# MCU_4G_SEN.net
KiCad netlist of a schematic drawn in Altium Designer
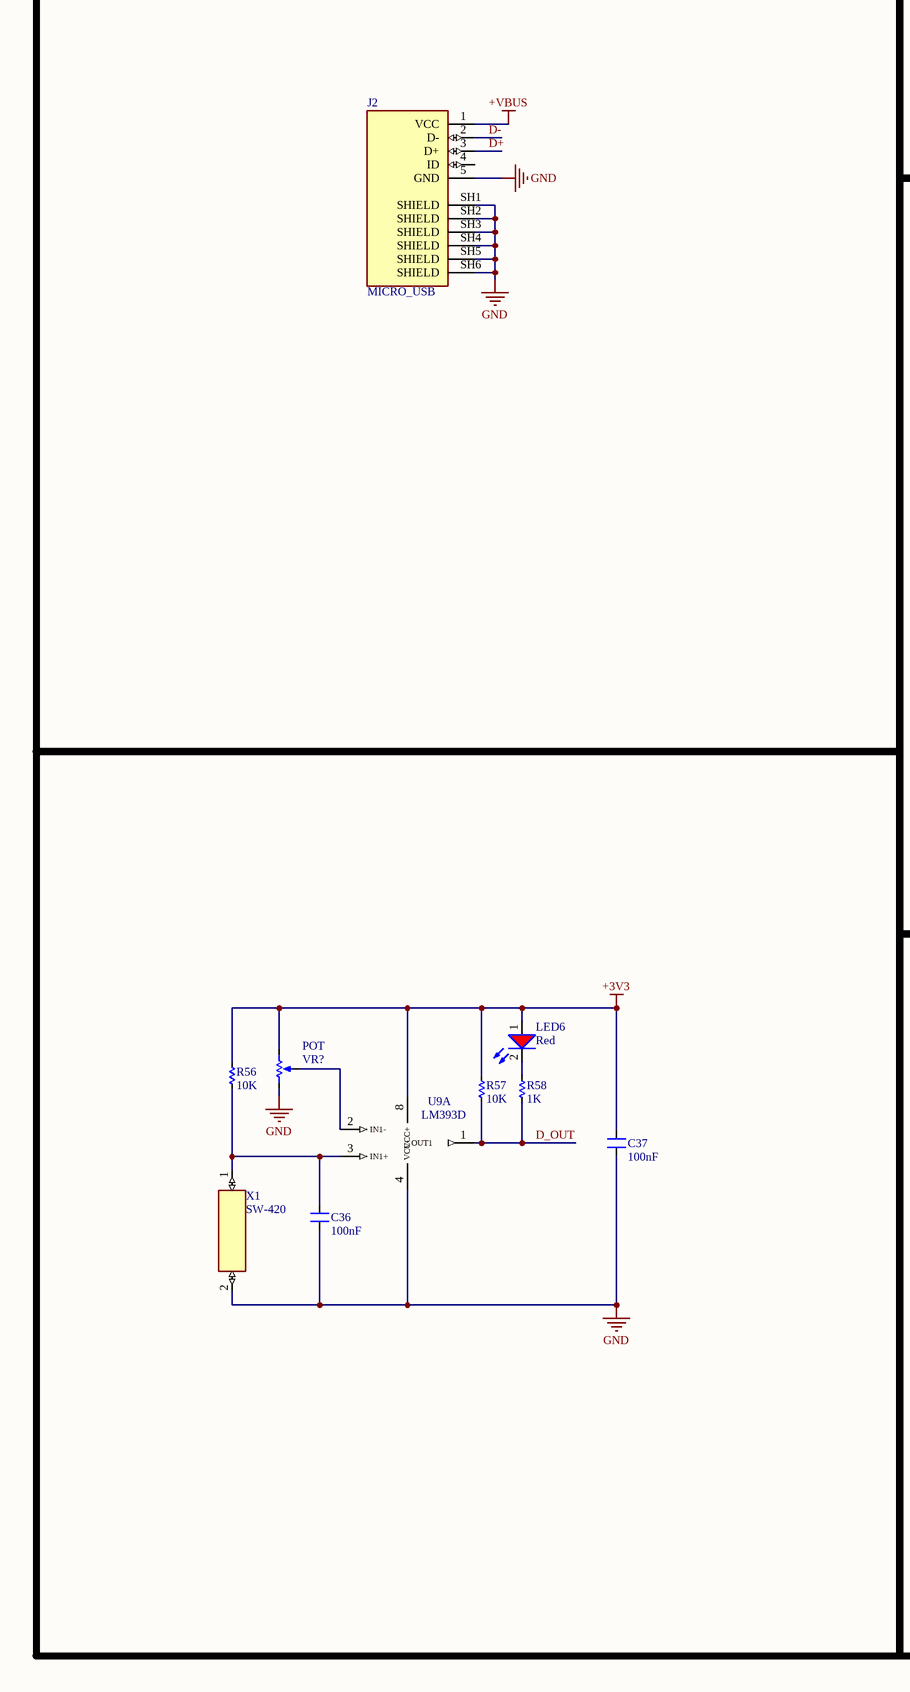
[diagram p0: MCU_4G_SEN.SchDoc, left]
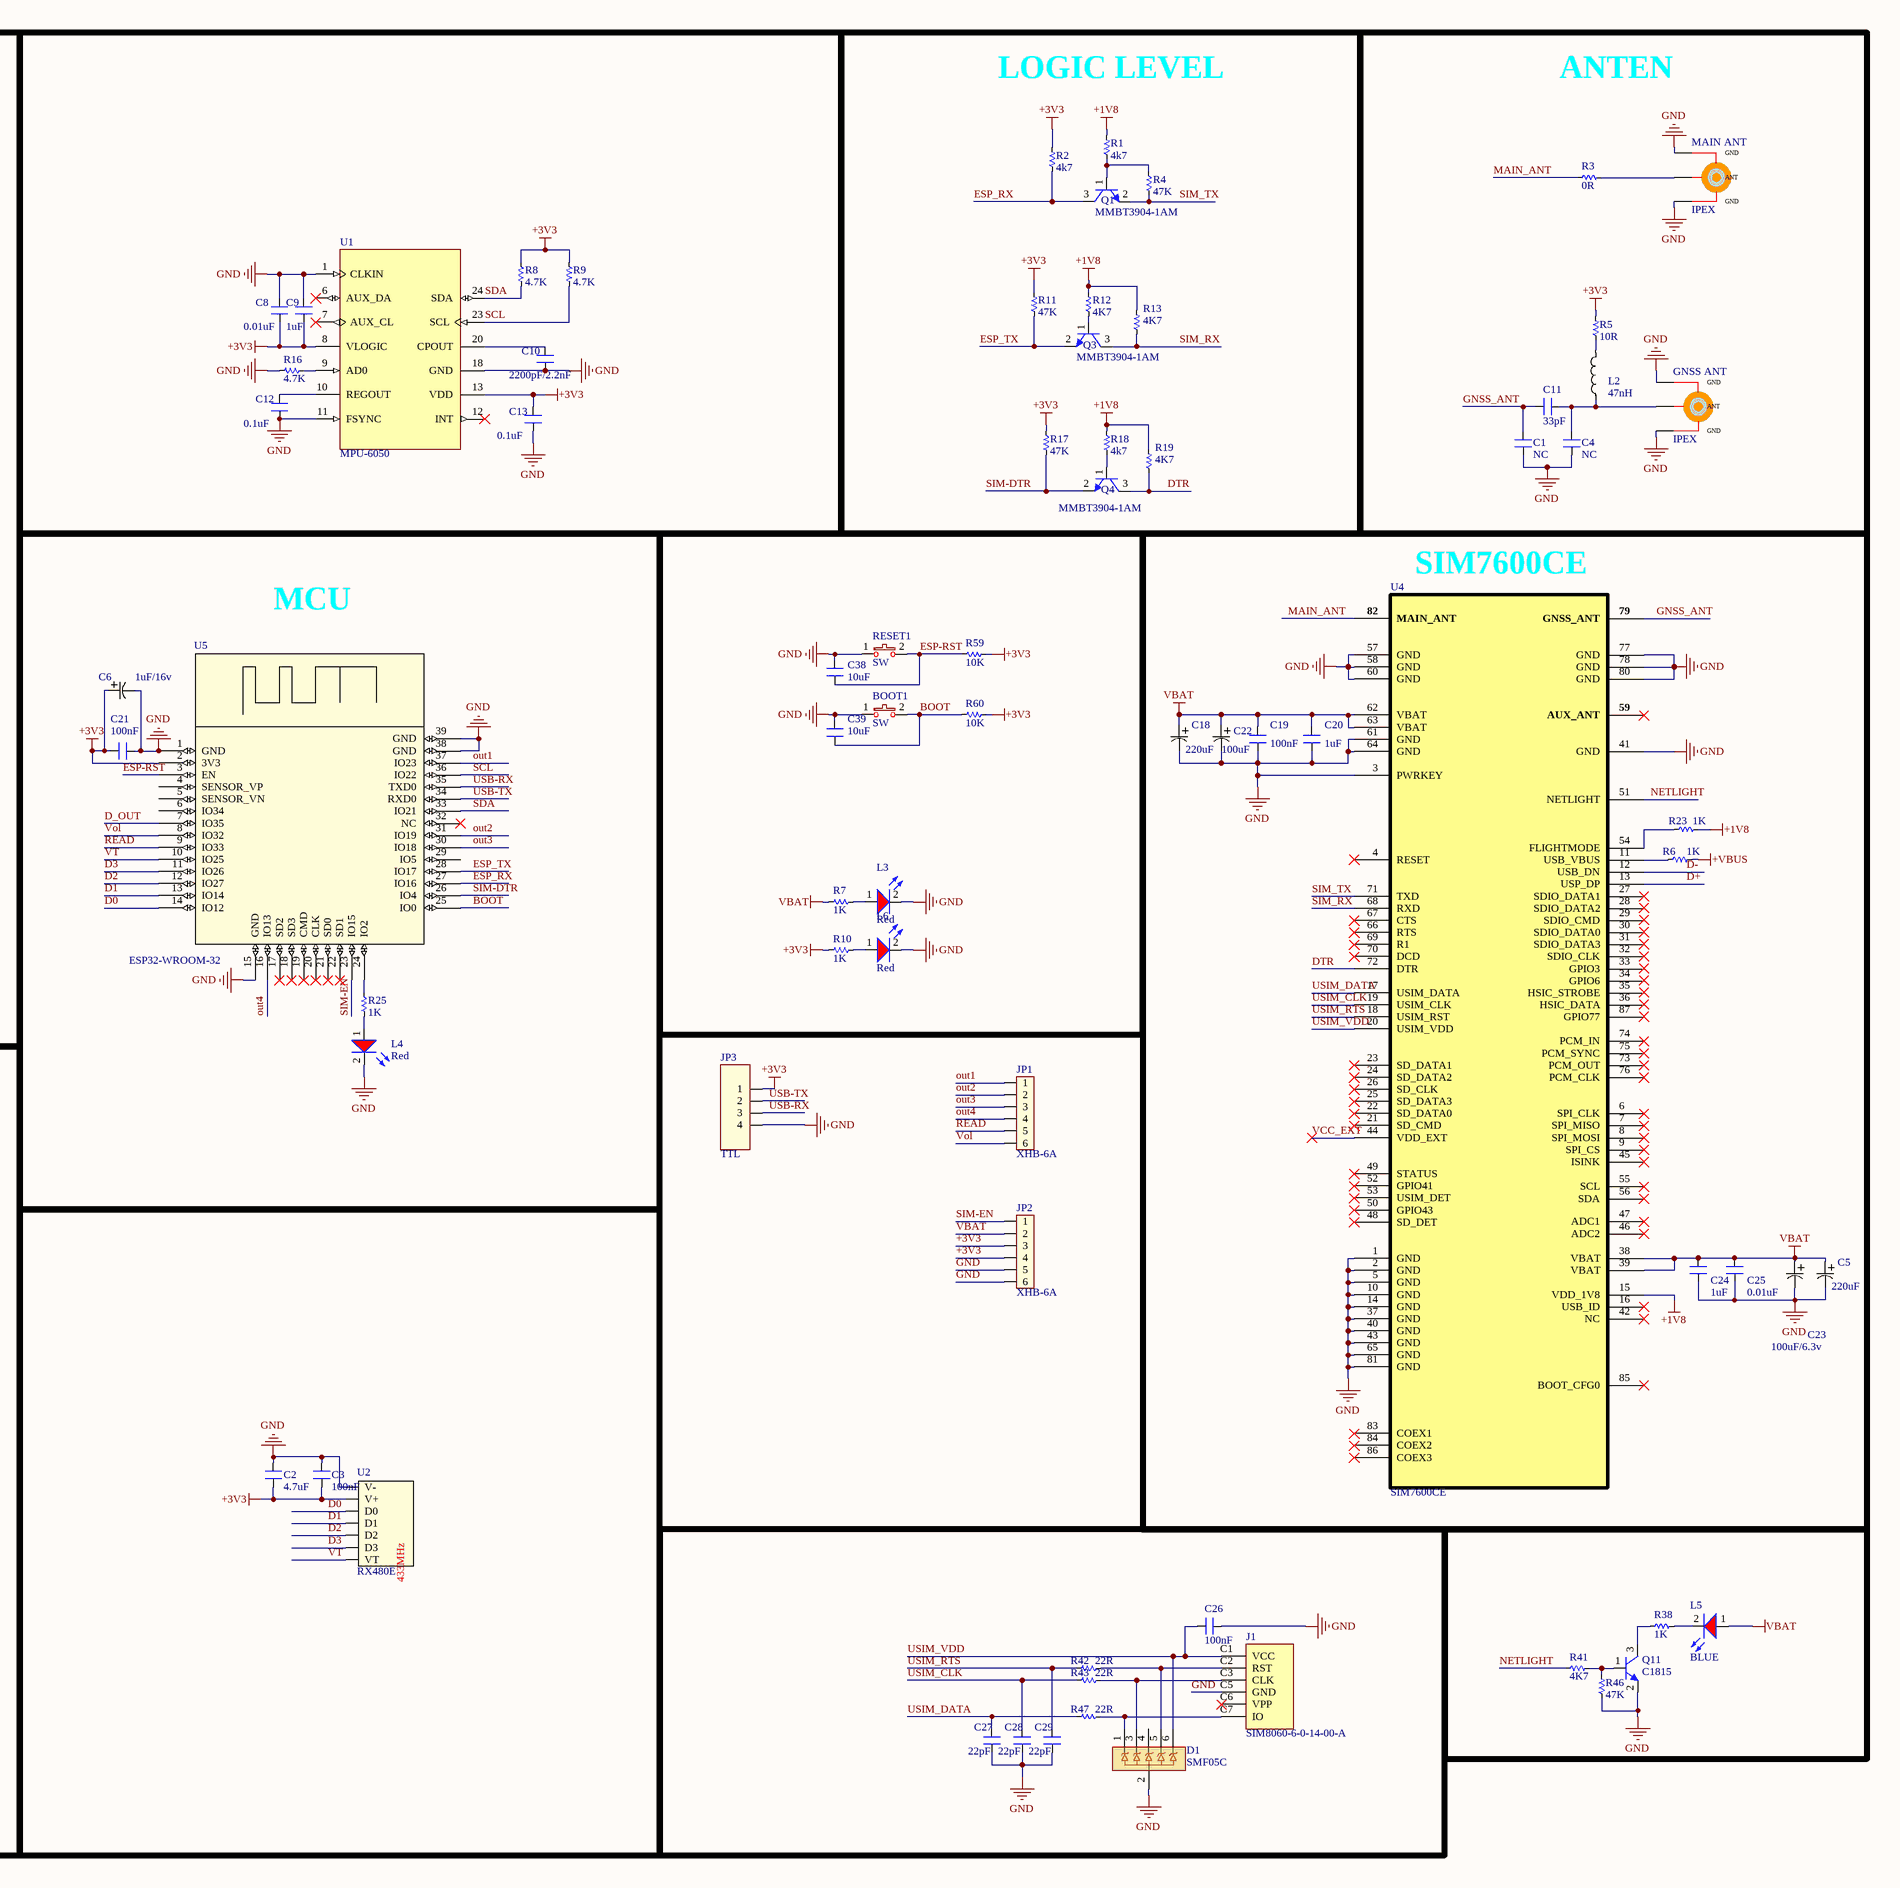
[diagram p1: MCU_4G_SEN.SchDoc, right]

(export (version "E")
  (design (tool "Eeschema 10.0.6"))
  (components
    (comp (ref "BOOT1")
      (value "SW")
      (footprint "BUTTON_3X4MM_2PIN")
      (libsource (lib "tuananh_smd") (part "BUTON2"))
    )
    (comp (ref "C1")
      (value "NC")
      (footprint "CAP-0603")
      (description "Cap np W0.3")
      (fields (field (name "COPYRIGHT") "VanDungEvn"))
      (libsource (lib "tuananh_smd") (part "CAP ko phan cuc"))
    )
    (comp (ref "C2")
      (value "4.7uF")
      (footprint "CAP-0603")
      (description "Cap np W0.3")
      (fields (field (name "COPYRIGHT") "VanDungEvn"))
      (libsource (lib "tuananh_smd") (part "CAP ko phan cuc"))
    )
    (comp (ref "C3")
      (value "100nF")
      (footprint "CAP-0603")
      (description "Cap np W0.3")
      (fields (field (name "COPYRIGHT") "VanDungEvn"))
      (libsource (lib "tuananh_smd") (part "CAP ko phan cuc"))
    )
    (comp (ref "C4")
      (value "NC")
      (footprint "CAP-0603")
      (description "Cap np W0.3")
      (fields (field (name "COPYRIGHT") "VanDungEvn"))
      (libsource (lib "tuananh_smd") (part "CAP ko phan cuc"))
    )
    (comp (ref "C5")
      (value "220uF")
      (footprint "CAP-TANTALUM-2312 - ( 6032M )")
      (libsource (lib "Tuấn Anh") (part "CAP_PHANCUCDEN"))
    )
    (comp (ref "C6")
      (value "1uF/16v")
      (footprint "CAP-TANTALUM-1206 - ( 3216 )")
      (libsource (lib "") (part "CAP_PHANCUCDEN_1"))
    )
    (comp (ref "C8")
      (value "0.01uF")
      (footprint "CAP-0603")
      (description "Cap np W0.3")
      (fields (field (name "COPYRIGHT") "VanDungEvn"))
      (libsource (lib "tuananh_smd") (part "CAP ko phan cuc"))
    )
    (comp (ref "C9")
      (value "1uF")
      (footprint "CAP-0603")
      (description "Cap np W0.3")
      (fields (field (name "COPYRIGHT") "VanDungEvn"))
      (libsource (lib "tuananh_smd") (part "CAP ko phan cuc"))
    )
    (comp (ref "C10")
      (value "2200pF/2.2nF")
      (footprint "CAP-0603")
      (description "Cap np W0.3")
      (fields (field (name "COPYRIGHT") "VanDungEvn"))
      (libsource (lib "tuananh_smd") (part "CAP ko phan cuc"))
    )
    (comp (ref "C11")
      (value "33pF")
      (footprint "CAP-0603")
      (description "Cap np W0.3")
      (fields (field (name "COPYRIGHT") "VanDungEvn"))
      (libsource (lib "tuananh_smd") (part "CAP ko phan cuc"))
    )
    (comp (ref "C12")
      (value "0.1uF")
      (footprint "CAP-0603")
      (description "Cap np W0.3")
      (fields (field (name "COPYRIGHT") "VanDungEvn"))
      (libsource (lib "tuananh_smd") (part "CAP ko phan cuc"))
    )
    (comp (ref "C13")
      (value "0.1uF")
      (footprint "CAP-0603")
      (description "Cap np W0.3")
      (fields (field (name "COPYRIGHT") "VanDungEvn"))
      (libsource (lib "tuananh_smd") (part "CAP ko phan cuc"))
    )
    (comp (ref "C18")
      (value "220uF")
      (footprint "CAP-TANTALUM-2312 - ( 6032M )")
      (libsource (lib "Tuấn Anh") (part "CAP_PHANCUCDEN"))
    )
    (comp (ref "C19")
      (value "100nF")
      (footprint "CAP-0603")
      (description "Cap np W0.3")
      (fields (field (name "COPYRIGHT") "VanDungEvn"))
      (libsource (lib "tuananh_smd") (part "CAP ko phan cuc"))
    )
    (comp (ref "C20")
      (value "1uF")
      (footprint "CAP-0603")
      (description "Cap np W0.3")
      (fields (field (name "COPYRIGHT") "VanDungEvn"))
      (libsource (lib "tuananh_smd") (part "CAP ko phan cuc"))
    )
    (comp (ref "C21")
      (value "100nF")
      (footprint "CAP-0603")
      (description "Cap np W0.3")
      (fields (field (name "COPYRIGHT") "VanDungEvn"))
      (libsource (lib "tuananh_smd") (part "CAP ko phan cuc"))
    )
    (comp (ref "C22")
      (value "100uF")
      (footprint "CAP-TANTALUM-1206 - ( 3216 )")
      (libsource (lib "Tuấn Anh") (part "CAP_PHANCUCDEN"))
    )
    (comp (ref "C23")
      (value "100uF/6.3v")
      (footprint "CAP-TANTALUM-1206 - ( 3216 )")
      (libsource (lib "Tuấn Anh") (part "CAP_PHANCUCDEN"))
    )
    (comp (ref "C24")
      (value "1uF")
      (footprint "CAP-0603")
      (description "Cap np W0.3")
      (fields (field (name "COPYRIGHT") "VanDungEvn"))
      (libsource (lib "tuananh_smd") (part "CAP ko phan cuc"))
    )
    (comp (ref "C25")
      (value "0.01uF")
      (footprint "CAP-0603")
      (description "Cap np W0.3")
      (fields (field (name "COPYRIGHT") "VanDungEvn"))
      (libsource (lib "tuananh_smd") (part "CAP ko phan cuc"))
    )
    (comp (ref "C26")
      (value "100nF")
      (footprint "CAP-0603")
      (description "Cap np W0.3")
      (fields (field (name "COPYRIGHT") "VanDungEvn"))
      (libsource (lib "tuananh_smd") (part "CAP ko phan cuc"))
    )
    (comp (ref "C27")
      (value "22pF")
      (footprint "CAP-0603")
      (description "Cap np W0.3")
      (fields (field (name "COPYRIGHT") "VanDungEvn"))
      (libsource (lib "tuananh_smd") (part "CAP ko phan cuc"))
    )
    (comp (ref "C28")
      (value "22pF")
      (footprint "CAP-0603")
      (description "Cap np W0.3")
      (fields (field (name "COPYRIGHT") "VanDungEvn"))
      (libsource (lib "tuananh_smd") (part "CAP ko phan cuc"))
    )
    (comp (ref "C29")
      (value "22pF")
      (footprint "CAP-0603")
      (description "Cap np W0.3")
      (fields (field (name "COPYRIGHT") "VanDungEvn"))
      (libsource (lib "tuananh_smd") (part "CAP ko phan cuc"))
    )
    (comp (ref "C36")
      (value "100nF")
      (footprint "CAP-0603")
      (description "Cap np W0.3")
      (fields (field (name "COPYRIGHT") "VanDungEvn"))
      (libsource (lib "tuananh_smd") (part "CAP ko phan cuc"))
    )
    (comp (ref "C37")
      (value "100nF")
      (footprint "CAP-0603")
      (description "Cap np W0.3")
      (fields (field (name "COPYRIGHT") "VanDungEvn"))
      (libsource (lib "tuananh_smd") (part "CAP ko phan cuc"))
    )
    (comp (ref "C38")
      (value "10uF")
      (footprint "CAP-0603")
      (description "Cap np W0.3")
      (fields (field (name "COPYRIGHT") "VanDungEvn"))
      (libsource (lib "tuananh_smd") (part "CAP ko phan cuc"))
    )
    (comp (ref "C39")
      (value "10uF")
      (footprint "CAP-0603")
      (description "Cap np W0.3")
      (fields (field (name "COPYRIGHT") "VanDungEvn"))
      (libsource (lib "tuananh_smd") (part "CAP ko phan cuc"))
    )
    (comp (ref "D1") (value "SMF05C") (footprint "SOT-363") (libsource (lib "tuananh_smd") (part "SMF05C")))
    (comp (ref "GNSS ANT")
      (value "IPEX")
      (footprint "IPEX-ANTEN")
      (libsource (lib "tuananh_smd") (part "IPEX-ANTEN"))
    )
    (comp (ref "J1")
      (value "SIM8060-6-0-14-00-A")
      (footprint "NanoSim_BKK")
      (description "6 Position Card Connector NANO SIM Surface Mount, Right Angle Gold")
      (fields (field (name "MF") "Global Connector Technology"))
      (libsource (lib "tuananh_smd") (part "NanoSim_SIM8060-6-0-14-00-A"))
    )
    (comp (ref "J2")
      (value "MICRO_USB")
      (footprint "MICRO_USB _PAD")
      (description "Micro USB, Input Output Connectors, B TYPE RECEPTACLE with flange")
      (fields (field (name "MF") "Amphenol ICC") (field (name "MP") "10118194-0001LF"))
      (libsource (lib "tuananh_smd") (part "MICRO_USB"))
    )
    (comp (ref "JP1")
      (value "XHB-6A")
      (footprint "XH2.54-6P_THRU")
      (description "JP6 PIN")
      (libsource (lib "Tuấn Anh") (part "JP6"))
    )
    (comp (ref "JP2")
      (value "XHB-6A")
      (footprint "XH2.54-6P_THRU")
      (description "JP6 PIN")
      (libsource (lib "Tuấn Anh") (part "JP6"))
    )
    (comp (ref "JP3") (value "TTL") (footprint "JP_4PIN") (libsource (lib "Tuấn Anh") (part "JP4")))
    (comp (ref "L2") (value "47nH") (footprint "IN-0603") (libsource (lib "tuananh_smd") (part "IN")))
    (comp (ref "L3")
      (value "Red")
      (footprint "LED_0805_smd")
      (description "LED Red 3mm/5MM")
      (fields (field (name "Comment") "LED"))
      (libsource (lib "tuananh_smd") (part "LED_RED_SMD"))
    )
    (comp (ref "L4")
      (value "Red")
      (footprint "LED_0805_smd")
      (description "LED Red 3mm/5MM")
      (fields (field (name "Comment") "LED"))
      (libsource (lib "tuananh_smd") (part "LED_RED_SMD"))
    )
    (comp (ref "L5")
      (value "BLUE")
      (footprint "LED_0805_smd")
      (description "LED Red 3mm/5MM")
      (fields (field (name "Comment") "LED"))
      (libsource (lib "tuananh_smd") (part "LED_RED_SMD"))
    )
    (comp (ref "L6")
      (value "Red")
      (footprint "LED_0805_smd")
      (description "LED Red 3mm/5MM")
      (fields (field (name "Comment") "LED"))
      (libsource (lib "tuananh_smd") (part "LED_RED_SMD"))
    )
    (comp (ref "LED6")
      (value "Red")
      (footprint "LED_0805_smd")
      (description "LED Red 3mm/5MM")
      (fields (field (name "Comment") "SMD"))
      (libsource (lib "tuananh_smd") (part "LED_RED_SMD"))
    )
    (comp (ref "MAIN ANT")
      (value "IPEX")
      (footprint "IPEX-ANTEN")
      (libsource (lib "tuananh_smd") (part "IPEX-ANTEN"))
    )
    (comp (ref "POT") (value "VR?") (footprint "Pot_trim") (libsource (lib "Vip") (part "Pot mini")))
    (comp (ref "Q1")
      (value "MMBT3904-1AM")
      (footprint "SOT-23")
      (description "Trans NPN 50V 150mA TO-92")
      (libsource (lib "tuananh_smd") (part "C1815-SMD"))
    )
    (comp (ref "Q3")
      (value "MMBT3904-1AM")
      (footprint "SOT-23")
      (description "Trans NPN 50V 150mA TO-92")
      (libsource (lib "tuananh_smd") (part "C1815-SMD"))
    )
    (comp (ref "Q4")
      (value "MMBT3904-1AM")
      (footprint "SOT-23")
      (description "Trans NPN 50V 150mA TO-92")
      (libsource (lib "tuananh_smd") (part "C1815-SMD"))
    )
    (comp (ref "Q11")
      (value "C1815")
      (footprint "SOT-23")
      (description "Trans NPN 50V 150mA TO-92")
      (libsource (lib "tuananh_smd") (part "C1815-SMD"))
    )
    (comp (ref "R1")
      (value "4k7")
      (footprint "RES-0603")
      (description "Res")
      (fields
        (field (name "MANUFACTURER") "Generic Components")
        (field (name "PUBLISHER") "Altium Hobart Technology Centre")
      )
      (libsource (lib "tuananh_smd") (part "Res"))
    )
    (comp (ref "R2")
      (value "4k7")
      (footprint "RES-0603")
      (description "Res")
      (fields
        (field (name "MANUFACTURER") "Generic Components")
        (field (name "PUBLISHER") "Altium Hobart Technology Centre")
      )
      (libsource (lib "tuananh_smd") (part "Res"))
    )
    (comp (ref "R3")
      (value "0R")
      (footprint "RES-0603")
      (description "Res")
      (fields
        (field (name "MANUFACTURER") "Generic Components")
        (field (name "PUBLISHER") "Altium Hobart Technology Centre")
      )
      (libsource (lib "tuananh_smd") (part "Res"))
    )
    (comp (ref "R4")
      (value "47K")
      (footprint "RES-0603")
      (description "Res")
      (fields
        (field (name "MANUFACTURER") "Generic Components")
        (field (name "PUBLISHER") "Altium Hobart Technology Centre")
      )
      (libsource (lib "tuananh_smd") (part "Res"))
    )
    (comp (ref "R5")
      (value "10R")
      (footprint "RES-0603")
      (description "Res")
      (fields
        (field (name "MANUFACTURER") "Generic Components")
        (field (name "PUBLISHER") "Altium Hobart Technology Centre")
      )
      (libsource (lib "tuananh_smd") (part "Res"))
    )
    (comp (ref "R6")
      (value "1K")
      (footprint "RES-0603")
      (description "Res")
      (fields
        (field (name "MANUFACTURER") "Generic Components")
        (field (name "PUBLISHER") "Altium Hobart Technology Centre")
      )
      (libsource (lib "tuananh_smd") (part "Res"))
    )
    (comp (ref "R7")
      (value "1K")
      (footprint "RES-0603")
      (description "Res")
      (fields
        (field (name "MANUFACTURER") "Generic Components")
        (field (name "PUBLISHER") "Altium Hobart Technology Centre")
      )
      (libsource (lib "tuananh_smd") (part "Res"))
    )
    (comp (ref "R8")
      (value "4.7K")
      (footprint "RES-0603")
      (description "Res")
      (fields
        (field (name "MANUFACTURER") "Generic Components")
        (field (name "PUBLISHER") "Altium Hobart Technology Centre")
      )
      (libsource (lib "Tuấn Anh") (part "Res"))
    )
    (comp (ref "R9")
      (value "4.7K")
      (footprint "RES-0603")
      (description "Res")
      (fields
        (field (name "MANUFACTURER") "Generic Components")
        (field (name "PUBLISHER") "Altium Hobart Technology Centre")
      )
      (libsource (lib "Tuấn Anh") (part "Res"))
    )
    (comp (ref "R10")
      (value "1K")
      (footprint "RES-0603")
      (description "Res")
      (fields
        (field (name "MANUFACTURER") "Generic Components")
        (field (name "PUBLISHER") "Altium Hobart Technology Centre")
      )
      (libsource (lib "tuananh_smd") (part "Res"))
    )
    (comp (ref "R11")
      (value "47K")
      (footprint "RES-0603")
      (description "Res")
      (fields
        (field (name "MANUFACTURER") "Generic Components")
        (field (name "PUBLISHER") "Altium Hobart Technology Centre")
      )
      (libsource (lib "tuananh_smd") (part "Res"))
    )
    (comp (ref "R12")
      (value "4K7")
      (footprint "RES-0603")
      (description "Res")
      (fields
        (field (name "MANUFACTURER") "Generic Components")
        (field (name "PUBLISHER") "Altium Hobart Technology Centre")
      )
      (libsource (lib "tuananh_smd") (part "Res"))
    )
    (comp (ref "R13")
      (value "4K7")
      (footprint "RES-0603")
      (description "Res")
      (fields
        (field (name "MANUFACTURER") "Generic Components")
        (field (name "PUBLISHER") "Altium Hobart Technology Centre")
      )
      (libsource (lib "tuananh_smd") (part "Res"))
    )
    (comp (ref "R16")
      (value "4.7K")
      (footprint "RES-0603")
      (description "Res")
      (fields
        (field (name "MANUFACTURER") "Generic Components")
        (field (name "PUBLISHER") "Altium Hobart Technology Centre")
      )
      (libsource (lib "Tuấn Anh") (part "Res"))
    )
    (comp (ref "R17")
      (value "47K")
      (footprint "RES-0603")
      (description "Res")
      (fields
        (field (name "MANUFACTURER") "Generic Components")
        (field (name "PUBLISHER") "Altium Hobart Technology Centre")
      )
      (libsource (lib "tuananh_smd") (part "Res"))
    )
    (comp (ref "R18")
      (value "4k7")
      (footprint "RES-0603")
      (description "Res")
      (fields
        (field (name "MANUFACTURER") "Generic Components")
        (field (name "PUBLISHER") "Altium Hobart Technology Centre")
      )
      (libsource (lib "tuananh_smd") (part "Res"))
    )
    (comp (ref "R19")
      (value "4K7")
      (footprint "RES-0603")
      (description "Res")
      (fields
        (field (name "MANUFACTURER") "Generic Components")
        (field (name "PUBLISHER") "Altium Hobart Technology Centre")
      )
      (libsource (lib "tuananh_smd") (part "Res"))
    )
    (comp (ref "R23")
      (value "1K")
      (footprint "RES-0603")
      (description "Res")
      (fields
        (field (name "MANUFACTURER") "Generic Components")
        (field (name "PUBLISHER") "Altium Hobart Technology Centre")
      )
      (libsource (lib "tuananh_smd") (part "Res"))
    )
    (comp (ref "R25")
      (value "1K")
      (footprint "RES-0603")
      (description "Res")
      (fields
        (field (name "MANUFACTURER") "Generic Components")
        (field (name "PUBLISHER") "Altium Hobart Technology Centre")
      )
      (libsource (lib "tuananh_smd") (part "Res"))
    )
    (comp (ref "R38")
      (value "1K")
      (footprint "RES-0603")
      (description "Res")
      (fields
        (field (name "MANUFACTURER") "Generic Components")
        (field (name "PUBLISHER") "Altium Hobart Technology Centre")
      )
      (libsource (lib "tuananh_smd") (part "Res"))
    )
    (comp (ref "R41")
      (value "4K7")
      (footprint "RES-0603")
      (description "Res")
      (fields
        (field (name "MANUFACTURER") "Generic Components")
        (field (name "PUBLISHER") "Altium Hobart Technology Centre")
      )
      (libsource (lib "tuananh_smd") (part "Res"))
    )
    (comp (ref "R42")
      (value "22R")
      (footprint "RES-0603")
      (description "Res")
      (fields
        (field (name "MANUFACTURER") "Generic Components")
        (field (name "PUBLISHER") "Altium Hobart Technology Centre")
      )
      (libsource (lib "tuananh_smd") (part "Res"))
    )
    (comp (ref "R43")
      (value "22R")
      (footprint "RES-0603")
      (description "Res")
      (fields
        (field (name "MANUFACTURER") "Generic Components")
        (field (name "PUBLISHER") "Altium Hobart Technology Centre")
      )
      (libsource (lib "tuananh_smd") (part "Res"))
    )
    (comp (ref "R46")
      (value "47K")
      (footprint "RES-0603")
      (description "Res")
      (fields
        (field (name "MANUFACTURER") "Generic Components")
        (field (name "PUBLISHER") "Altium Hobart Technology Centre")
      )
      (libsource (lib "tuananh_smd") (part "Res"))
    )
    (comp (ref "R47")
      (value "22R")
      (footprint "RES-0603")
      (description "Res")
      (fields
        (field (name "MANUFACTURER") "Generic Components")
        (field (name "PUBLISHER") "Altium Hobart Technology Centre")
      )
      (libsource (lib "tuananh_smd") (part "Res"))
    )
    (comp (ref "R56")
      (value "10K")
      (footprint "RES-0603")
      (description "Res")
      (fields
        (field (name "MANUFACTURER") "Generic Components")
        (field (name "PUBLISHER") "Altium Hobart Technology Centre")
      )
      (libsource (lib "Tuấn Anh") (part "Res"))
    )
    (comp (ref "R57")
      (value "10K")
      (footprint "RES-0603")
      (description "Res")
      (fields
        (field (name "MANUFACTURER") "Generic Components")
        (field (name "PUBLISHER") "Altium Hobart Technology Centre")
      )
      (libsource (lib "Tuấn Anh") (part "Res"))
    )
    (comp (ref "R58")
      (value "1K")
      (footprint "RES-0603")
      (description "Res")
      (fields
        (field (name "MANUFACTURER") "Generic Components")
        (field (name "PUBLISHER") "Altium Hobart Technology Centre")
      )
      (libsource (lib "Tuấn Anh") (part "Res"))
    )
    (comp (ref "R59")
      (value "10K")
      (footprint "RES-0603")
      (description "Res")
      (fields
        (field (name "MANUFACTURER") "Generic Components")
        (field (name "PUBLISHER") "Altium Hobart Technology Centre")
      )
      (libsource (lib "Tuấn Anh") (part "Res"))
    )
    (comp (ref "R60")
      (value "10K")
      (footprint "RES-0603")
      (description "Res")
      (fields
        (field (name "MANUFACTURER") "Generic Components")
        (field (name "PUBLISHER") "Altium Hobart Technology Centre")
      )
      (libsource (lib "Tuấn Anh") (part "Res"))
    )
    (comp (ref "RESET1")
      (value "SW")
      (footprint "BUTTON_3X4MM_2PIN")
      (libsource (lib "tuananh_smd") (part "BUTON2"))
    )
    (comp (ref "U1")
      (value "MPU-6050")
      (footprint "QFN-24")
      (libsource (lib "tuananh_smd") (part "MPU-6050"))
    )
    (comp (ref "U2") (value "RX480E") (footprint "RX480E") (libsource (lib "Tuấn Anh") (part "RX480E")))
    (comp (ref "U4")
      (value "SIM7600CE")
      (footprint "SIM7600C")
      (libsource (lib "tuananh_smd") (part "SIM7600CE*"))
    )
    (comp (ref "U5")
      (value "ESP32-WROOM-32")
      (footprint "ESP32-WROOM-32D")
      (libsource (lib "tuananh_smd") (part "ESP32-WROOM-32"))
    )
    (comp (ref "U9") (value "LM393D") (footprint "SOIC-8") (libsource (lib "tuananh_smd") (part "LM393D")))
    (comp (ref "X1")
      (value "SW-420")
      (footprint "SW-420")
      (description "ç”µåŠ›å˜åŽ‹å™¨ 2500Vrms 6VA 6 ç«¯å­ PC å¼•è„šé€šå­”")
      (fields (field (name "MF") "Stancor"))
      (libsource (lib "tuananh_smd") (part "SW-420"))
    )
  )
  (nets
    (net (code "1") (name "+1V8") (class "Default")
      (node (ref "R1") (pin "1") (pinfunction "1_1") (pintype "passive"))
      (node (ref "R12") (pin "1") (pinfunction "1_1") (pintype "passive"))
      (node (ref "R13") (pin "1") (pinfunction "1_1") (pintype "passive"))
      (node (ref "R18") (pin "1") (pinfunction "1_1") (pintype "passive"))
      (node (ref "R19") (pin "1") (pinfunction "1_1") (pintype "passive"))
      (node (ref "R23") (pin "1") (pinfunction "1_1") (pintype "passive"))
      (node (ref "U4") (pin "15") (pinfunction "VDD_1V8_15") (pintype "passive"))
    )
    (net (code "2") (name "+3V3") (class "Default")
      (node (ref "C13") (pin "2") (pinfunction "2_2") (pintype "passive"))
      (node (ref "C2") (pin "1") (pinfunction "1_1") (pintype "passive"))
      (node (ref "C21") (pin "1") (pinfunction "1_1") (pintype "passive"))
      (node (ref "C3") (pin "1") (pinfunction "1_1") (pintype "passive"))
      (node (ref "C37") (pin "2") (pinfunction "2_2") (pintype "passive"))
      (node (ref "C6") (pin "1") (pinfunction "1_1") (pintype "passive"))
      (node (ref "C8") (pin "1") (pinfunction "1_1") (pintype "passive"))
      (node (ref "C9") (pin "1") (pinfunction "1_1") (pintype "passive"))
      (node (ref "JP2") (pin "3") (pinfunction "3_3") (pintype "passive"))
      (node (ref "JP2") (pin "4") (pinfunction "4_4") (pintype "passive"))
      (node (ref "JP3") (pin "1") (pinfunction "1_1") (pintype "passive"))
      (node (ref "LED6") (pin "1") (pinfunction "A_1") (pintype "passive"))
      (node (ref "POT") (pin "3") (pinfunction "BOT_3") (pintype "passive"))
      (node (ref "R10") (pin "1") (pinfunction "1_1") (pintype "passive"))
      (node (ref "R11") (pin "1") (pinfunction "1_1") (pintype "passive"))
      (node (ref "R17") (pin "1") (pinfunction "1_1") (pintype "passive"))
      (node (ref "R2") (pin "1") (pinfunction "1_1") (pintype "passive"))
      (node (ref "R5") (pin "1") (pinfunction "1_1") (pintype "passive"))
      (node (ref "R56") (pin "1") (pinfunction "1_1") (pintype "passive"))
      (node (ref "R57") (pin "1") (pinfunction "1_1") (pintype "passive"))
      (node (ref "R59") (pin "2") (pinfunction "2_2") (pintype "passive"))
      (node (ref "R60") (pin "2") (pinfunction "2_2") (pintype "passive"))
      (node (ref "R8") (pin "2") (pinfunction "2_2") (pintype "passive"))
      (node (ref "R9") (pin "2") (pinfunction "2_2") (pintype "passive"))
      (node (ref "U1") (pin "13") (pinfunction "VDD_13") (pintype "power_in"))
      (node (ref "U1") (pin "8") (pinfunction "VLOGIC_8") (pintype "power_in"))
      (node (ref "U2") (pin "2") (pinfunction "V+_2") (pintype "passive"))
      (node (ref "U5") (pin "2") (pinfunction "3V3_2") (pintype "bidirectional"))
      (node (ref "U9") (pin "8") (pinfunction "VCC+_8") (pintype "power_in"))
    )
    (net (code "3") (name "+VBUS") (class "Default")
      (node (ref "J2") (pin "1") (pinfunction "VCC_1") (pintype "power_in"))
      (node (ref "R6") (pin "1") (pinfunction "1_1") (pintype "passive"))
    )
    (net (code "5") (name "/BOOT") (class "Default")
      (node (ref "BOOT1") (pin "2") (pinfunction "2_2") (pintype "passive"))
      (node (ref "C39") (pin "2") (pinfunction "2_2") (pintype "passive"))
      (node (ref "R60") (pin "1") (pinfunction "1_1") (pintype "passive"))
      (node (ref "U5") (pin "25") (pinfunction "IO0_25") (pintype "bidirectional"))
    )
    (net (code "6") (name "/D+") (class "Default")
      (node (ref "J2") (pin "3") (pinfunction "D+_3") (pintype "bidirectional"))
      (node (ref "U4") (pin "13") (pinfunction "USP_DP_13") (pintype "passive"))
    )
    (net (code "7") (name "/D-") (class "Default")
      (node (ref "J2") (pin "2") (pinfunction "D-_2") (pintype "bidirectional"))
      (node (ref "U4") (pin "12") (pinfunction "USB_DN_12") (pintype "passive"))
    )
    (net (code "8") (name "/D0") (class "Default")
      (node (ref "U2") (pin "3") (pinfunction "D0_3") (pintype "passive"))
      (node (ref "U5") (pin "14") (pinfunction "IO12_14") (pintype "bidirectional"))
    )
    (net (code "9") (name "/D1") (class "Default")
      (node (ref "U2") (pin "4") (pinfunction "D1_4") (pintype "passive"))
      (node (ref "U5") (pin "13") (pinfunction "IO14_13") (pintype "bidirectional"))
    )
    (net (code "10") (name "/D2") (class "Default")
      (node (ref "U2") (pin "5") (pinfunction "D2_5") (pintype "passive"))
      (node (ref "U5") (pin "12") (pinfunction "IO27_12") (pintype "bidirectional"))
    )
    (net (code "11") (name "/D3") (class "Default")
      (node (ref "U2") (pin "6") (pinfunction "D3_6") (pintype "passive"))
      (node (ref "U5") (pin "11") (pinfunction "IO26_11") (pintype "bidirectional"))
    )
    (net (code "12") (name "/DTR") (class "Default")
      (node (ref "Q4") (pin "3") (pinfunction "C_3") (pintype "passive"))
      (node (ref "R19") (pin "2") (pinfunction "2_2") (pintype "passive"))
      (node (ref "U4") (pin "72") (pinfunction "DTR_72") (pintype "passive"))
    )
    (net (code "13") (name "/D_OUT") (class "Default")
      (node (ref "R57") (pin "2") (pinfunction "2_2") (pintype "passive"))
      (node (ref "R58") (pin "2") (pinfunction "2_2") (pintype "passive"))
      (node (ref "U5") (pin "7") (pinfunction "IO35_7") (pintype "bidirectional"))
      (node (ref "U9") (pin "1") (pinfunction "OUT1_1") (pintype "output"))
    )
    (net (code "14") (name "/ESP-RST") (class "Default")
      (node (ref "C38") (pin "2") (pinfunction "2_2") (pintype "passive"))
      (node (ref "R59") (pin "1") (pinfunction "1_1") (pintype "passive"))
      (node (ref "RESET1") (pin "2") (pinfunction "2_2") (pintype "passive"))
      (node (ref "U5") (pin "3") (pinfunction "EN_3") (pintype "bidirectional"))
    )
    (net (code "15") (name "/ESP_RX") (class "Default")
      (node (ref "Q1") (pin "3") (pinfunction "C_3") (pintype "passive"))
      (node (ref "R2") (pin "2") (pinfunction "2_2") (pintype "passive"))
      (node (ref "U5") (pin "27") (pinfunction "IO16_27") (pintype "bidirectional"))
    )
    (net (code "16") (name "/ESP_TX") (class "Default")
      (node (ref "Q3") (pin "2") (pinfunction "E_2") (pintype "passive"))
      (node (ref "R11") (pin "2") (pinfunction "2_2") (pintype "passive"))
      (node (ref "U5") (pin "28") (pinfunction "IO17_28") (pintype "bidirectional"))
    )
    (net (code "17") (name "/GNSS_ANT") (class "Default")
      (node (ref "C1") (pin "2") (pinfunction "2_2") (pintype "passive"))
      (node (ref "C11") (pin "1") (pinfunction "1_1") (pintype "passive"))
      (node (ref "U4") (pin "79") (pinfunction "GNSS_ANT_79") (pintype "passive"))
    )
    (net (code "18") (name "/MAIN_ANT") (class "Default")
      (node (ref "R3") (pin "2") (pinfunction "2_2") (pintype "passive"))
      (node (ref "U4") (pin "82") (pinfunction "MAIN_ANT_82") (pintype "passive"))
    )
    (net (code "19") (name "/NETLIGHT") (class "Default")
      (node (ref "R41") (pin "2") (pinfunction "2_2") (pintype "passive"))
      (node (ref "U4") (pin "51") (pinfunction "NETLIGHT_51") (pintype "passive"))
    )
    (net (code "20") (name "/READ") (class "Default")
      (node (ref "JP1") (pin "5") (pinfunction "5_5") (pintype "passive"))
      (node (ref "U5") (pin "9") (pinfunction "IO33_9") (pintype "bidirectional"))
    )
    (net (code "21") (name "/SCL") (class "Default")
      (node (ref "R9") (pin "1") (pinfunction "1_1") (pintype "passive"))
      (node (ref "U1") (pin "23") (pinfunction "SCL_23") (pintype "input"))
      (node (ref "U5") (pin "36") (pinfunction "IO22_36") (pintype "bidirectional"))
    )
    (net (code "22") (name "/SDA") (class "Default")
      (node (ref "R8") (pin "1") (pinfunction "1_1") (pintype "passive"))
      (node (ref "U1") (pin "24") (pinfunction "SDA_24") (pintype "bidirectional"))
      (node (ref "U5") (pin "33") (pinfunction "IO21_33") (pintype "bidirectional"))
    )
    (net (code "23") (name "/SIM-DTR") (class "Default")
      (node (ref "Q4") (pin "2") (pinfunction "E_2") (pintype "passive"))
      (node (ref "R17") (pin "2") (pinfunction "2_2") (pintype "passive"))
      (node (ref "U5") (pin "26") (pinfunction "IO4_26") (pintype "bidirectional"))
    )
    (net (code "24") (name "/SIM-EN") (class "Default")
      (node (ref "JP2") (pin "1") (pinfunction "1_1") (pintype "passive"))
      (node (ref "U5") (pin "23") (pinfunction "IO15_23") (pintype "bidirectional"))
    )
    (net (code "25") (name "/SIM_RX") (class "Default")
      (node (ref "Q3") (pin "3") (pinfunction "C_3") (pintype "passive"))
      (node (ref "R13") (pin "2") (pinfunction "2_2") (pintype "passive"))
      (node (ref "U4") (pin "68") (pinfunction "RXD_68") (pintype "passive"))
    )
    (net (code "26") (name "/SIM_TX") (class "Default")
      (node (ref "Q1") (pin "2") (pinfunction "E_2") (pintype "passive"))
      (node (ref "R4") (pin "2") (pinfunction "2_2") (pintype "passive"))
      (node (ref "U4") (pin "71") (pinfunction "TXD_71") (pintype "passive"))
    )
    (net (code "27") (name "/USB-RX") (class "Default")
      (node (ref "JP3") (pin "3") (pinfunction "3_3") (pintype "passive"))
      (node (ref "U5") (pin "35") (pinfunction "TXD0_35") (pintype "bidirectional"))
    )
    (net (code "28") (name "/USB-TX") (class "Default")
      (node (ref "JP3") (pin "2") (pinfunction "2_2") (pintype "passive"))
      (node (ref "U5") (pin "34") (pinfunction "RXD0_34") (pintype "bidirectional"))
    )
    (net (code "29") (name "/USIM_CLK") (class "Default")
      (node (ref "C28") (pin "1") (pinfunction "1_1") (pintype "passive"))
      (node (ref "R43") (pin "1") (pinfunction "1_1") (pintype "passive"))
      (node (ref "U4") (pin "19") (pinfunction "USIM_CLK_19") (pintype "passive"))
    )
    (net (code "30") (name "/USIM_DATA") (class "Default")
      (node (ref "C27") (pin "1") (pinfunction "1_1") (pintype "passive"))
      (node (ref "R47") (pin "1") (pinfunction "1_1") (pintype "passive"))
      (node (ref "U4") (pin "17") (pinfunction "USIM_DATA_17") (pintype "passive"))
    )
    (net (code "31") (name "/USIM_RTS") (class "Default")
      (node (ref "C29") (pin "1") (pinfunction "1_1") (pintype "passive"))
      (node (ref "R42") (pin "1") (pinfunction "1_1") (pintype "passive"))
      (node (ref "U4") (pin "18") (pinfunction "USIM_RST_18") (pintype "passive"))
    )
    (net (code "32") (name "/USIM_VDD") (class "Default")
      (node (ref "C26") (pin "1") (pinfunction "1_1") (pintype "passive"))
      (node (ref "D1") (pin "6") (pinfunction "C6_6") (pintype "passive"))
      (node (ref "J1") (pin "C1") (pinfunction "VCC_C1") (pintype "passive"))
      (node (ref "U4") (pin "20") (pinfunction "USIM_VDD_20") (pintype "passive"))
    )
    (net (code "33") (name "/VCC_EXT") (class "Default")
      (node (ref "U4") (pin "44") (pinfunction "VDD_EXT_44") (pintype "passive+no_connect"))
    )
    (net (code "34") (name "/VT") (class "Default")
      (node (ref "U2") (pin "7") (pinfunction "VT_7") (pintype "passive"))
      (node (ref "U5") (pin "10") (pinfunction "IO25_10") (pintype "bidirectional"))
    )
    (net (code "35") (name "/Vol") (class "Default")
      (node (ref "JP1") (pin "6") (pinfunction "6_6") (pintype "passive"))
      (node (ref "U5") (pin "8") (pinfunction "IO32_8") (pintype "bidirectional"))
    )
    (net (code "36") (name "/out1") (class "Default")
      (node (ref "JP1") (pin "1") (pinfunction "1_1") (pintype "passive"))
      (node (ref "U5") (pin "37") (pinfunction "IO23_37") (pintype "bidirectional"))
    )
    (net (code "37") (name "/out2") (class "Default")
      (node (ref "JP1") (pin "2") (pinfunction "2_2") (pintype "passive"))
      (node (ref "U5") (pin "31") (pinfunction "IO19_31") (pintype "bidirectional"))
    )
    (net (code "38") (name "/out3") (class "Default")
      (node (ref "JP1") (pin "3") (pinfunction "3_3") (pintype "passive"))
      (node (ref "U5") (pin "30") (pinfunction "IO18_30") (pintype "bidirectional"))
    )
    (net (code "39") (name "/out4") (class "Default")
      (node (ref "JP1") (pin "4") (pinfunction "4_4") (pintype "passive"))
      (node (ref "U5") (pin "16") (pinfunction "IO13_16") (pintype "bidirectional"))
    )
    (net (code "40") (name "GND") (class "Default")
      (node (ref "BOOT1") (pin "1") (pinfunction "1_1") (pintype "passive"))
      (node (ref "C1") (pin "1") (pinfunction "1_1") (pintype "passive"))
      (node (ref "C10") (pin "1") (pinfunction "1_1") (pintype "passive"))
      (node (ref "C12") (pin "1") (pinfunction "1_1") (pintype "passive"))
      (node (ref "C13") (pin "1") (pinfunction "1_1") (pintype "passive"))
      (node (ref "C18") (pin "2") (pinfunction "2_2") (pintype "passive"))
      (node (ref "C19") (pin "1") (pinfunction "1_1") (pintype "passive"))
      (node (ref "C2") (pin "2") (pinfunction "2_2") (pintype "passive"))
      (node (ref "C20") (pin "1") (pinfunction "1_1") (pintype "passive"))
      (node (ref "C21") (pin "2") (pinfunction "2_2") (pintype "passive"))
      (node (ref "C22") (pin "2") (pinfunction "2_2") (pintype "passive"))
      (node (ref "C23") (pin "2") (pinfunction "2_2") (pintype "passive"))
      (node (ref "C24") (pin "1") (pinfunction "1_1") (pintype "passive"))
      (node (ref "C25") (pin "1") (pinfunction "1_1") (pintype "passive"))
      (node (ref "C26") (pin "2") (pinfunction "2_2") (pintype "passive"))
      (node (ref "C27") (pin "2") (pinfunction "2_2") (pintype "passive"))
      (node (ref "C28") (pin "2") (pinfunction "2_2") (pintype "passive"))
      (node (ref "C29") (pin "2") (pinfunction "2_2") (pintype "passive"))
      (node (ref "C3") (pin "2") (pinfunction "2_2") (pintype "passive"))
      (node (ref "C36") (pin "1") (pinfunction "1_1") (pintype "passive"))
      (node (ref "C37") (pin "1") (pinfunction "1_1") (pintype "passive"))
      (node (ref "C38") (pin "1") (pinfunction "1_1") (pintype "passive"))
      (node (ref "C39") (pin "1") (pinfunction "1_1") (pintype "passive"))
      (node (ref "C4") (pin "1") (pinfunction "1_1") (pintype "passive"))
      (node (ref "C5") (pin "2") (pinfunction "2_2") (pintype "passive"))
      (node (ref "C6") (pin "2") (pinfunction "2_2") (pintype "passive"))
      (node (ref "C8") (pin "2") (pinfunction "2_2") (pintype "passive"))
      (node (ref "C9") (pin "2") (pinfunction "2_2") (pintype "passive"))
      (node (ref "D1") (pin "2") (pinfunction "C2_2") (pintype "passive"))
      (node (ref "GNSS ANT") (pin "1") (pinfunction "GND_1") (pintype "passive"))
      (node (ref "GNSS ANT") (pin "3") (pinfunction "GND_3") (pintype "passive"))
      (node (ref "J1") (pin "C5") (pinfunction "GND_C5") (pintype "passive"))
      (node (ref "J2") (pin "5") (pinfunction "GND_5") (pintype "power_in"))
      (node (ref "J2") (pin "SH1") (pinfunction "SHIELD_SH1") (pintype "passive"))
      (node (ref "J2") (pin "SH2") (pinfunction "SHIELD_SH2") (pintype "passive"))
      (node (ref "J2") (pin "SH3") (pinfunction "SHIELD_SH3") (pintype "passive"))
      (node (ref "J2") (pin "SH4") (pinfunction "SHIELD_SH4") (pintype "passive"))
      (node (ref "J2") (pin "SH5") (pinfunction "SHIELD_SH5") (pintype "passive"))
      (node (ref "J2") (pin "SH6") (pinfunction "SHIELD_SH6") (pintype "passive"))
      (node (ref "JP2") (pin "5") (pinfunction "5_5") (pintype "passive"))
      (node (ref "JP2") (pin "6") (pinfunction "6_6") (pintype "passive"))
      (node (ref "JP3") (pin "4") (pinfunction "4_4") (pintype "passive"))
      (node (ref "L3") (pin "2") (pinfunction "K_2") (pintype "passive"))
      (node (ref "L4") (pin "2") (pinfunction "K_2") (pintype "passive"))
      (node (ref "L6") (pin "2") (pinfunction "K_2") (pintype "passive"))
      (node (ref "MAIN ANT") (pin "1") (pinfunction "GND_1") (pintype "passive"))
      (node (ref "MAIN ANT") (pin "3") (pinfunction "GND_3") (pintype "passive"))
      (node (ref "POT") (pin "1") (pinfunction "TOP_1") (pintype "passive"))
      (node (ref "Q11") (pin "2") (pinfunction "E_2") (pintype "passive"))
      (node (ref "R16") (pin "1") (pinfunction "1_1") (pintype "passive"))
      (node (ref "R46") (pin "2") (pinfunction "2_2") (pintype "passive"))
      (node (ref "RESET1") (pin "1") (pinfunction "1_1") (pintype "passive"))
      (node (ref "U1") (pin "1") (pinfunction "CLKIN_1") (pintype "input"))
      (node (ref "U1") (pin "11") (pinfunction "FSYNC_11") (pintype "input"))
      (node (ref "U1") (pin "18") (pinfunction "GND_18") (pintype "power_in"))
      (node (ref "U2") (pin "1") (pinfunction "V-_1") (pintype "passive"))
      (node (ref "U4") (pin "1") (pinfunction "GND_1") (pintype "passive"))
      (node (ref "U4") (pin "10") (pinfunction "GND_10") (pintype "passive"))
      (node (ref "U4") (pin "14") (pinfunction "GND_14") (pintype "passive"))
      (node (ref "U4") (pin "2") (pinfunction "GND_2") (pintype "passive"))
      (node (ref "U4") (pin "3") (pinfunction "PWRKEY_3") (pintype "passive"))
      (node (ref "U4") (pin "37") (pinfunction "GND_37") (pintype "passive"))
      (node (ref "U4") (pin "40") (pinfunction "GND_40") (pintype "passive"))
      (node (ref "U4") (pin "41") (pinfunction "GND_41") (pintype "passive"))
      (node (ref "U4") (pin "43") (pinfunction "GND_43") (pintype "passive"))
      (node (ref "U4") (pin "5") (pinfunction "GND_5") (pintype "passive"))
      (node (ref "U4") (pin "57") (pinfunction "GND_57") (pintype "passive"))
      (node (ref "U4") (pin "58") (pinfunction "GND_58") (pintype "passive"))
      (node (ref "U4") (pin "60") (pinfunction "GND_60") (pintype "passive"))
      (node (ref "U4") (pin "61") (pinfunction "GND_61") (pintype "passive"))
      (node (ref "U4") (pin "64") (pinfunction "GND_64") (pintype "passive"))
      (node (ref "U4") (pin "65") (pinfunction "GND_65") (pintype "passive"))
      (node (ref "U4") (pin "77") (pinfunction "GND_77") (pintype "passive"))
      (node (ref "U4") (pin "78") (pinfunction "GND_78") (pintype "passive"))
      (node (ref "U4") (pin "80") (pinfunction "GND_80") (pintype "passive"))
      (node (ref "U4") (pin "81") (pinfunction "GND_81") (pintype "passive"))
      (node (ref "U5") (pin "1") (pinfunction "GND_1") (pintype "bidirectional"))
      (node (ref "U5") (pin "15") (pinfunction "GND_15") (pintype "bidirectional"))
      (node (ref "U5") (pin "38") (pinfunction "GND_38") (pintype "bidirectional"))
      (node (ref "U5") (pin "39") (pinfunction "GND_39") (pintype "bidirectional"))
      (node (ref "U9") (pin "4") (pinfunction "VCC-_4") (pintype "power_in"))
      (node (ref "X1") (pin "2") (pinfunction "2_2") (pintype "bidirectional"))
    )
    (net (code "41") (name "Net-(D1-C1)") (class "Default")
      (node (ref "D1") (pin "1") (pinfunction "C1_1") (pintype "passive"))
      (node (ref "J1") (pin "C7") (pinfunction "IO_C7") (pintype "passive"))
      (node (ref "R47") (pin "2") (pinfunction "2_2") (pintype "passive"))
    )
    (net (code "42") (name "Net-(D1-C3)") (class "Default")
      (node (ref "D1") (pin "3") (pinfunction "C3_3") (pintype "passive"))
      (node (ref "J1") (pin "C3") (pinfunction "CLK_C3") (pintype "passive"))
      (node (ref "R43") (pin "2") (pinfunction "2_2") (pintype "passive"))
    )
    (net (code "43") (name "Net-(D1-C5)") (class "Default")
      (node (ref "D1") (pin "5") (pinfunction "C5_5") (pintype "passive"))
      (node (ref "J1") (pin "C2") (pinfunction "RST_C2") (pintype "passive"))
      (node (ref "R42") (pin "2") (pinfunction "2_2") (pintype "passive"))
    )
    (net (code "44") (name "Net-(GNSS ANT-ANT)") (class "Default")
      (node (ref "C11") (pin "2") (pinfunction "2_2") (pintype "passive"))
      (node (ref "C4") (pin "2") (pinfunction "2_2") (pintype "passive"))
      (node (ref "GNSS ANT") (pin "2") (pinfunction "ANT_2") (pintype "passive"))
      (node (ref "L2") (pin "1") (pinfunction "1_1") (pintype "passive"))
    )
    (net (code "45") (name "Net-(L2-Pad2)") (class "Default")
      (node (ref "L2") (pin "2") (pinfunction "2_2") (pintype "passive"))
      (node (ref "R5") (pin "2") (pinfunction "2_2") (pintype "passive"))
    )
    (net (code "46") (name "Net-(L3-A)") (class "Default")
      (node (ref "L3") (pin "1") (pinfunction "A_1") (pintype "passive"))
      (node (ref "R7") (pin "2") (pinfunction "2_2") (pintype "passive"))
    )
    (net (code "47") (name "Net-(L4-A)") (class "Default")
      (node (ref "L4") (pin "1") (pinfunction "A_1") (pintype "passive"))
      (node (ref "R25") (pin "2") (pinfunction "2_2") (pintype "passive"))
    )
    (net (code "48") (name "Net-(L5-K)") (class "Default")
      (node (ref "L5") (pin "2") (pinfunction "K_2") (pintype "passive"))
      (node (ref "R38") (pin "1") (pinfunction "1_1") (pintype "passive"))
    )
    (net (code "49") (name "Net-(L6-A)") (class "Default")
      (node (ref "L6") (pin "1") (pinfunction "A_1") (pintype "passive"))
      (node (ref "R10") (pin "2") (pinfunction "2_2") (pintype "passive"))
    )
    (net (code "50") (name "Net-(LED6-K)") (class "Default")
      (node (ref "LED6") (pin "2") (pinfunction "K_2") (pintype "passive"))
      (node (ref "R58") (pin "1") (pinfunction "1_1") (pintype "passive"))
    )
    (net (code "51") (name "Net-(MAIN ANT-ANT)") (class "Default")
      (node (ref "MAIN ANT") (pin "2") (pinfunction "ANT_2") (pintype "passive"))
      (node (ref "R3") (pin "1") (pinfunction "1_1") (pintype "passive"))
    )
    (net (code "52") (name "Net-(POT-TAP)") (class "Default")
      (node (ref "POT") (pin "2") (pinfunction "TAP_2") (pintype "passive"))
      (node (ref "U9") (pin "2") (pinfunction "IN1-_2") (pintype "input"))
    )
    (net (code "53") (name "Net-(Q1-B)") (class "Default")
      (node (ref "Q1") (pin "1") (pinfunction "B_1") (pintype "passive"))
      (node (ref "R1") (pin "2") (pinfunction "2_2") (pintype "passive"))
      (node (ref "R4") (pin "1") (pinfunction "1_1") (pintype "passive"))
    )
    (net (code "54") (name "Net-(Q3-B)") (class "Default")
      (node (ref "Q3") (pin "1") (pinfunction "B_1") (pintype "passive"))
      (node (ref "R12") (pin "2") (pinfunction "2_2") (pintype "passive"))
    )
    (net (code "55") (name "Net-(Q4-B)") (class "Default")
      (node (ref "Q4") (pin "1") (pinfunction "B_1") (pintype "passive"))
      (node (ref "R18") (pin "2") (pinfunction "2_2") (pintype "passive"))
    )
    (net (code "56") (name "Net-(Q11-B)") (class "Default")
      (node (ref "Q11") (pin "1") (pinfunction "B_1") (pintype "passive"))
      (node (ref "R41") (pin "1") (pinfunction "1_1") (pintype "passive"))
      (node (ref "R46") (pin "1") (pinfunction "1_1") (pintype "passive"))
    )
    (net (code "57") (name "Net-(Q11-C)") (class "Default")
      (node (ref "Q11") (pin "3") (pinfunction "C_3") (pintype "passive"))
      (node (ref "R38") (pin "2") (pinfunction "2_2") (pintype "passive"))
    )
    (net (code "58") (name "Net-(U1-AD0)") (class "Default")
      (node (ref "R16") (pin "2") (pinfunction "2_2") (pintype "passive"))
      (node (ref "U1") (pin "9") (pinfunction "AD0_9") (pintype "input"))
    )
    (net (code "59") (name "Net-(U1-CPOUT)") (class "Default")
      (node (ref "C10") (pin "2") (pinfunction "2_2") (pintype "passive"))
      (node (ref "U1") (pin "20") (pinfunction "CPOUT_20") (pintype "passive"))
    )
    (net (code "60") (name "Net-(U1-REGOUT)") (class "Default")
      (node (ref "C12") (pin "2") (pinfunction "2_2") (pintype "passive"))
      (node (ref "U1") (pin "10") (pinfunction "REGOUT_10") (pintype "passive"))
    )
    (net (code "61") (name "Net-(U4-FLIGHTMODE)") (class "Default")
      (node (ref "R23") (pin "2") (pinfunction "2_2") (pintype "passive"))
      (node (ref "U4") (pin "54") (pinfunction "FLIGHTMODE_54") (pintype "passive"))
    )
    (net (code "62") (name "Net-(U4-USB_VBUS)") (class "Default")
      (node (ref "R6") (pin "2") (pinfunction "2_2") (pintype "passive"))
      (node (ref "U4") (pin "11") (pinfunction "USB_VBUS_11") (pintype "passive"))
    )
    (net (code "63") (name "Net-(U5-IO2)") (class "Default")
      (node (ref "R25") (pin "1") (pinfunction "1_1") (pintype "passive"))
      (node (ref "U5") (pin "24") (pinfunction "IO2_24") (pintype "bidirectional"))
    )
    (net (code "64") (name "Net-(U9A-IN1+)") (class "Default")
      (node (ref "C36") (pin "2") (pinfunction "2_2") (pintype "passive"))
      (node (ref "R56") (pin "2") (pinfunction "2_2") (pintype "passive"))
      (node (ref "U9") (pin "3") (pinfunction "IN1+_3") (pintype "input"))
      (node (ref "X1") (pin "1") (pinfunction "1_1") (pintype "bidirectional"))
    )
    (net (code "65") (name "VBAT") (class "Default")
      (node (ref "C18") (pin "1") (pinfunction "1_1") (pintype "passive"))
      (node (ref "C19") (pin "2") (pinfunction "2_2") (pintype "passive"))
      (node (ref "C20") (pin "2") (pinfunction "2_2") (pintype "passive"))
      (node (ref "C22") (pin "1") (pinfunction "1_1") (pintype "passive"))
      (node (ref "C23") (pin "1") (pinfunction "1_1") (pintype "passive"))
      (node (ref "C24") (pin "2") (pinfunction "2_2") (pintype "passive"))
      (node (ref "C25") (pin "2") (pinfunction "2_2") (pintype "passive"))
      (node (ref "C5") (pin "1") (pinfunction "1_1") (pintype "passive"))
      (node (ref "JP2") (pin "2") (pinfunction "2_2") (pintype "passive"))
      (node (ref "L5") (pin "1") (pinfunction "A_1") (pintype "passive"))
      (node (ref "R7") (pin "1") (pinfunction "1_1") (pintype "passive"))
      (node (ref "U4") (pin "38") (pinfunction "VBAT_38") (pintype "passive"))
      (node (ref "U4") (pin "39") (pinfunction "VBAT_39") (pintype "passive"))
      (node (ref "U4") (pin "62") (pinfunction "VBAT_62") (pintype "passive"))
      (node (ref "U4") (pin "63") (pinfunction "VBAT_63") (pintype "passive"))
    )
    (net (code "66") (name "unconnected-(D1-C4-Pad4)") (class "Default")
      (node (ref "D1") (pin "4") (pinfunction "C4_4") (pintype "passive"))
    )
    (net (code "67") (name "unconnected-(J1-VPP-PadC6)") (class "Default")
      (node (ref "J1") (pin "C6") (pinfunction "VPP_C6") (pintype "passive+no_connect"))
    )
    (net (code "68") (name "unconnected-(J2-ID-Pad4)") (class "Default")
      (node (ref "J2") (pin "4") (pinfunction "ID_4") (pintype "bidirectional"))
    )
    (net (code "69") (name "unconnected-(U1-AUX_CL-Pad7)") (class "Default")
      (node (ref "U1") (pin "7") (pinfunction "AUX_CL_7") (pintype "output+no_connect"))
    )
    (net (code "70") (name "unconnected-(U1-AUX_DA-Pad6)") (class "Default")
      (node (ref "U1") (pin "6") (pinfunction "AUX_DA_6") (pintype "bidirectional+no_connect"))
    )
    (net (code "71") (name "unconnected-(U1-INT-Pad12)") (class "Default")
      (node (ref "U1") (pin "12") (pinfunction "INT_12") (pintype "output+no_connect"))
    )
    (net (code "72") (name "unconnected-(U4-ADC1-Pad47)") (class "Default")
      (node (ref "U4") (pin "47") (pinfunction "ADC1_47") (pintype "passive+no_connect"))
    )
    (net (code "73") (name "unconnected-(U4-ADC2-Pad46)") (class "Default")
      (node (ref "U4") (pin "46") (pinfunction "ADC2_46") (pintype "passive+no_connect"))
    )
    (net (code "74") (name "unconnected-(U4-AUX_ANT-Pad59)") (class "Default")
      (node (ref "U4") (pin "59") (pinfunction "AUX_ANT_59") (pintype "passive+no_connect"))
    )
    (net (code "75") (name "unconnected-(U4-BOOT_CFG0-Pad85)") (class "Default")
      (node (ref "U4") (pin "85") (pinfunction "BOOT_CFG0_85") (pintype "passive+no_connect"))
    )
    (net (code "76") (name "unconnected-(U4-COEX1-Pad83)") (class "Default")
      (node (ref "U4") (pin "83") (pinfunction "COEX1_83") (pintype "passive+no_connect"))
    )
    (net (code "77") (name "unconnected-(U4-COEX2-Pad84)") (class "Default")
      (node (ref "U4") (pin "84") (pinfunction "COEX2_84") (pintype "passive+no_connect"))
    )
    (net (code "78") (name "unconnected-(U4-COEX3-Pad86)") (class "Default")
      (node (ref "U4") (pin "86") (pinfunction "COEX3_86") (pintype "passive+no_connect"))
    )
    (net (code "79") (name "unconnected-(U4-CTS-Pad67)") (class "Default")
      (node (ref "U4") (pin "67") (pinfunction "CTS_67") (pintype "passive+no_connect"))
    )
    (net (code "80") (name "unconnected-(U4-DCD-Pad70)") (class "Default")
      (node (ref "U4") (pin "70") (pinfunction "DCD_70") (pintype "passive+no_connect"))
    )
    (net (code "81") (name "unconnected-(U4-GPIO3-Pad33)") (class "Default")
      (node (ref "U4") (pin "33") (pinfunction "GPIO3_33") (pintype "passive"))
    )
    (net (code "82") (name "unconnected-(U4-GPIO6-Pad34)") (class "Default")
      (node (ref "U4") (pin "34") (pinfunction "GPIO6_34") (pintype "passive"))
    )
    (net (code "83") (name "unconnected-(U4-GPIO41-Pad52)") (class "Default")
      (node (ref "U4") (pin "52") (pinfunction "GPIO41_52") (pintype "passive+no_connect"))
    )
    (net (code "84") (name "unconnected-(U4-GPIO43-Pad50)") (class "Default")
      (node (ref "U4") (pin "50") (pinfunction "GPIO43_50") (pintype "passive+no_connect"))
    )
    (net (code "85") (name "unconnected-(U4-GPIO77-Pad87)") (class "Default")
      (node (ref "U4") (pin "87") (pinfunction "GPIO77_87") (pintype "passive"))
    )
    (net (code "86") (name "unconnected-(U4-HSIC_DATA-Pad36)") (class "Default")
      (node (ref "U4") (pin "36") (pinfunction "HSIC_DATA_36") (pintype "passive"))
    )
    (net (code "87") (name "unconnected-(U4-HSIC_STROBE-Pad35)") (class "Default")
      (node (ref "U4") (pin "35") (pinfunction "HSIC_STROBE_35") (pintype "passive"))
    )
    (net (code "88") (name "unconnected-(U4-ISINK-Pad45)") (class "Default")
      (node (ref "U4") (pin "45") (pinfunction "ISINK_45") (pintype "passive+no_connect"))
    )
    (net (code "89") (name "unconnected-(U4-NC-Pad42)") (class "Default")
      (node (ref "U4") (pin "42") (pinfunction "NC_42") (pintype "passive+no_connect"))
    )
    (net (code "90") (name "unconnected-(U4-PCM_CLK-Pad76)") (class "Default")
      (node (ref "U4") (pin "76") (pinfunction "PCM_CLK_76") (pintype "passive+no_connect"))
    )
    (net (code "91") (name "unconnected-(U4-PCM_IN-Pad74)") (class "Default")
      (node (ref "U4") (pin "74") (pinfunction "PCM_IN_74") (pintype "passive+no_connect"))
    )
    (net (code "92") (name "unconnected-(U4-PCM_OUT-Pad73)") (class "Default")
      (node (ref "U4") (pin "73") (pinfunction "PCM_OUT_73") (pintype "passive+no_connect"))
    )
    (net (code "93") (name "unconnected-(U4-PCM_SYNC-Pad75)") (class "Default")
      (node (ref "U4") (pin "75") (pinfunction "PCM_SYNC_75") (pintype "passive+no_connect"))
    )
    (net (code "94") (name "unconnected-(U4-R1-Pad69)") (class "Default")
      (node (ref "U4") (pin "69") (pinfunction "R1_69") (pintype "passive+no_connect"))
    )
    (net (code "95") (name "unconnected-(U4-RESET-Pad4)") (class "Default")
      (node (ref "U4") (pin "4") (pinfunction "RESET_4") (pintype "passive"))
    )
    (net (code "96") (name "unconnected-(U4-RTS-Pad66)") (class "Default")
      (node (ref "U4") (pin "66") (pinfunction "RTS_66") (pintype "passive+no_connect"))
    )
    (net (code "97") (name "unconnected-(U4-SCL-Pad55)") (class "Default")
      (node (ref "U4") (pin "55") (pinfunction "SCL_55") (pintype "passive+no_connect"))
    )
    (net (code "98") (name "unconnected-(U4-SDA-Pad56)") (class "Default")
      (node (ref "U4") (pin "56") (pinfunction "SDA_56") (pintype "passive+no_connect"))
    )
    (net (code "99") (name "unconnected-(U4-SDIO_CLK-Pad32)") (class "Default")
      (node (ref "U4") (pin "32") (pinfunction "SDIO_CLK_32") (pintype "passive"))
    )
    (net (code "100") (name "unconnected-(U4-SDIO_CMD-Pad29)") (class "Default")
      (node (ref "U4") (pin "29") (pinfunction "SDIO_CMD_29") (pintype "passive"))
    )
    (net (code "101") (name "unconnected-(U4-SDIO_DATA0-Pad30)") (class "Default")
      (node (ref "U4") (pin "30") (pinfunction "SDIO_DATA0_30") (pintype "passive"))
    )
    (net (code "102") (name "unconnected-(U4-SDIO_DATA1-Pad27)") (class "Default")
      (node (ref "U4") (pin "27") (pinfunction "SDIO_DATA1_27") (pintype "passive+no_connect"))
    )
    (net (code "103") (name "unconnected-(U4-SDIO_DATA2-Pad28)") (class "Default")
      (node (ref "U4") (pin "28") (pinfunction "SDIO_DATA2_28") (pintype "passive"))
    )
    (net (code "104") (name "unconnected-(U4-SDIO_DATA3-Pad31)") (class "Default")
      (node (ref "U4") (pin "31") (pinfunction "SDIO_DATA3_31") (pintype "passive"))
    )
    (net (code "105") (name "unconnected-(U4-SD_CLK-Pad26)") (class "Default")
      (node (ref "U4") (pin "26") (pinfunction "SD_CLK_26") (pintype "passive+no_connect"))
    )
    (net (code "106") (name "unconnected-(U4-SD_CMD-Pad21)") (class "Default")
      (node (ref "U4") (pin "21") (pinfunction "SD_CMD_21") (pintype "passive+no_connect"))
    )
    (net (code "107") (name "unconnected-(U4-SD_DATA0-Pad22)") (class "Default")
      (node (ref "U4") (pin "22") (pinfunction "SD_DATA0_22") (pintype "passive+no_connect"))
    )
    (net (code "108") (name "unconnected-(U4-SD_DATA1-Pad23)") (class "Default")
      (node (ref "U4") (pin "23") (pinfunction "SD_DATA1_23") (pintype "passive+no_connect"))
    )
    (net (code "109") (name "unconnected-(U4-SD_DATA2-Pad24)") (class "Default")
      (node (ref "U4") (pin "24") (pinfunction "SD_DATA2_24") (pintype "passive+no_connect"))
    )
    (net (code "110") (name "unconnected-(U4-SD_DATA3-Pad25)") (class "Default")
      (node (ref "U4") (pin "25") (pinfunction "SD_DATA3_25") (pintype "passive+no_connect"))
    )
    (net (code "111") (name "unconnected-(U4-SD_DET-Pad48)") (class "Default")
      (node (ref "U4") (pin "48") (pinfunction "SD_DET_48") (pintype "passive+no_connect"))
    )
    (net (code "112") (name "unconnected-(U4-SPI_CLK-Pad6)") (class "Default")
      (node (ref "U4") (pin "6") (pinfunction "SPI_CLK_6") (pintype "passive+no_connect"))
    )
    (net (code "113") (name "unconnected-(U4-SPI_CS-Pad9)") (class "Default")
      (node (ref "U4") (pin "9") (pinfunction "SPI_CS_9") (pintype "passive+no_connect"))
    )
    (net (code "114") (name "unconnected-(U4-SPI_MISO-Pad7)") (class "Default")
      (node (ref "U4") (pin "7") (pinfunction "SPI_MISO_7") (pintype "passive+no_connect"))
    )
    (net (code "115") (name "unconnected-(U4-SPI_MOSI-Pad8)") (class "Default")
      (node (ref "U4") (pin "8") (pinfunction "SPI_MOSI_8") (pintype "passive+no_connect"))
    )
    (net (code "116") (name "unconnected-(U4-STATUS-Pad49)") (class "Default")
      (node (ref "U4") (pin "49") (pinfunction "STATUS_49") (pintype "passive+no_connect"))
    )
    (net (code "117") (name "unconnected-(U4-USB_ID-Pad16)") (class "Default")
      (node (ref "U4") (pin "16") (pinfunction "USB_ID_16") (pintype "passive+no_connect"))
    )
    (net (code "118") (name "unconnected-(U4-USIM_DET-Pad53)") (class "Default")
      (node (ref "U4") (pin "53") (pinfunction "USIM_DET_53") (pintype "passive+no_connect"))
    )
    (net (code "119") (name "unconnected-(U5-CLK-Pad20)") (class "Default")
      (node (ref "U5") (pin "20") (pinfunction "CLK_20") (pintype "bidirectional+no_connect"))
    )
    (net (code "120") (name "unconnected-(U5-CMD-Pad19)") (class "Default")
      (node (ref "U5") (pin "19") (pinfunction "CMD_19") (pintype "bidirectional+no_connect"))
    )
    (net (code "121") (name "unconnected-(U5-IO5-Pad29)") (class "Default")
      (node (ref "U5") (pin "29") (pinfunction "IO5_29") (pintype "bidirectional"))
    )
    (net (code "122") (name "unconnected-(U5-IO34-Pad6)") (class "Default")
      (node (ref "U5") (pin "6") (pinfunction "IO34_6") (pintype "bidirectional"))
    )
    (net (code "123") (name "unconnected-(U5-NC-Pad32)") (class "Default")
      (node (ref "U5") (pin "32") (pinfunction "NC_32") (pintype "bidirectional+no_connect"))
    )
    (net (code "124") (name "unconnected-(U5-SD0-Pad21)") (class "Default")
      (node (ref "U5") (pin "21") (pinfunction "SD0_21") (pintype "bidirectional+no_connect"))
    )
    (net (code "125") (name "unconnected-(U5-SD1-Pad22)") (class "Default")
      (node (ref "U5") (pin "22") (pinfunction "SD1_22") (pintype "bidirectional+no_connect"))
    )
    (net (code "126") (name "unconnected-(U5-SD2-Pad17)") (class "Default")
      (node (ref "U5") (pin "17") (pinfunction "SD2_17") (pintype "bidirectional+no_connect"))
    )
    (net (code "127") (name "unconnected-(U5-SD3-Pad18)") (class "Default")
      (node (ref "U5") (pin "18") (pinfunction "SD3_18") (pintype "bidirectional+no_connect"))
    )
    (net (code "128") (name "unconnected-(U5-SENSOR_VN-Pad5)") (class "Default")
      (node (ref "U5") (pin "5") (pinfunction "SENSOR_VN_5") (pintype "bidirectional"))
    )
    (net (code "129") (name "unconnected-(U5-SENSOR_VP-Pad4)") (class "Default")
      (node (ref "U5") (pin "4") (pinfunction "SENSOR_VP_4") (pintype "bidirectional"))
    )
  )
)
